# 11_-MAIN_POWER2.net
KiCad netlist of a schematic drawn in Altium Designer
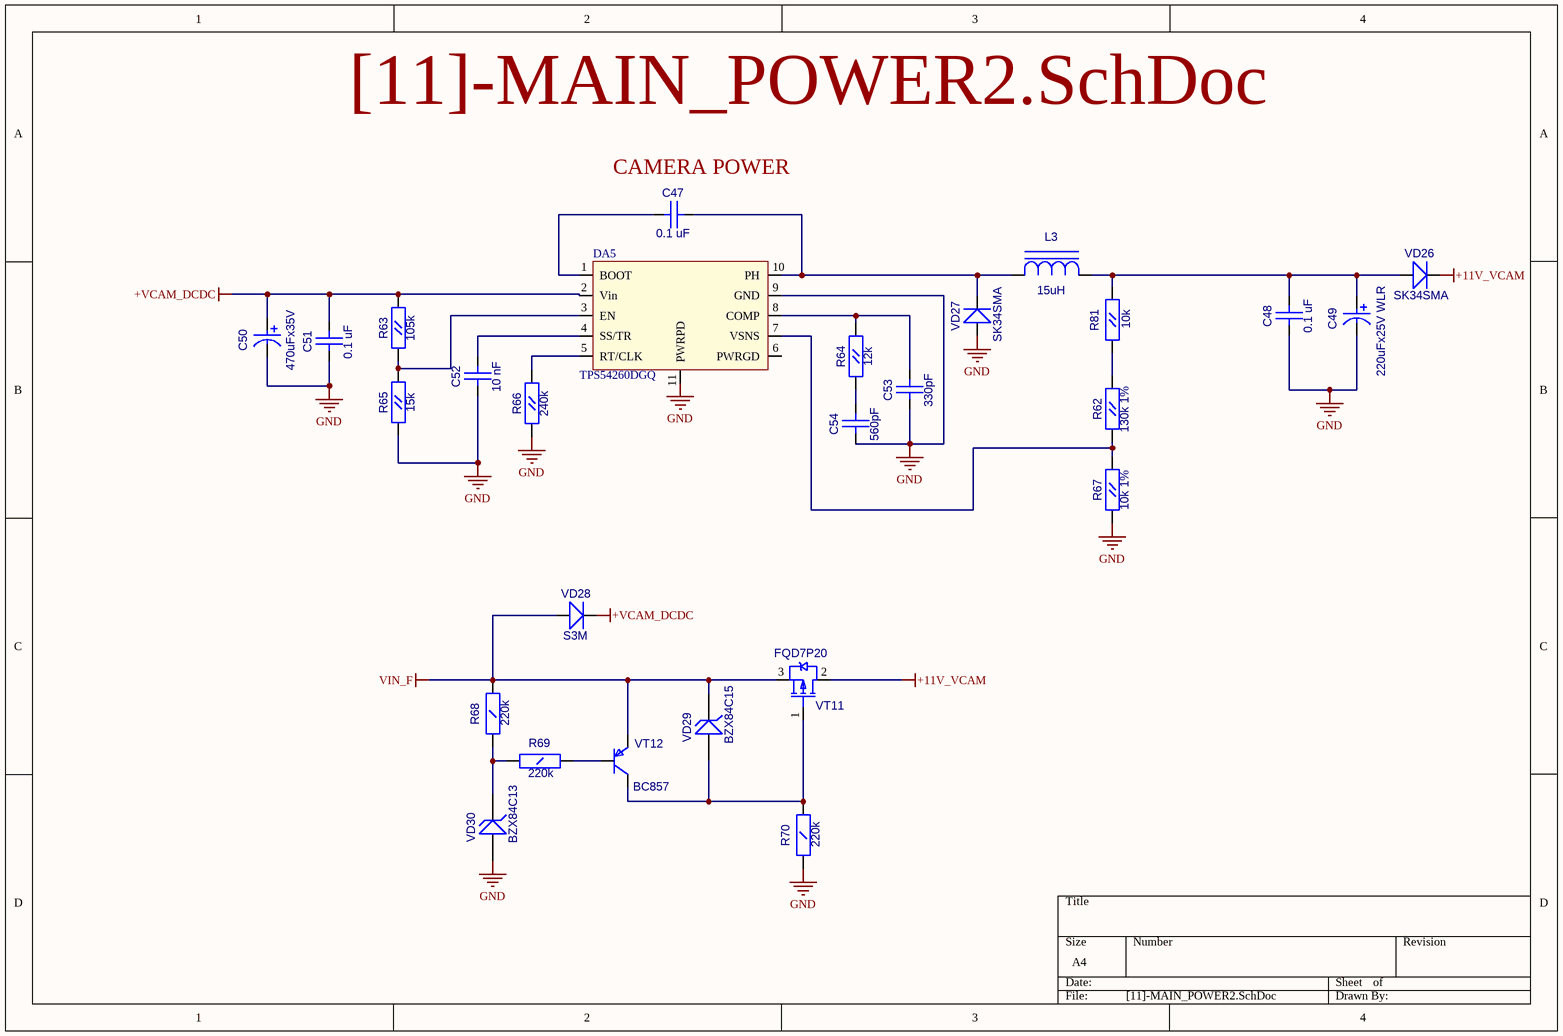
[diagram p0: [11]-MAIN_POWER2.SchDoc]

(export (version "E")
  (design (tool "Eeschema 10.0.6"))
  (components
    (comp (ref "C47")
      (value "0.1 uF")
      (footprint "CC0603")
      (description "CC0603")
      (libsource (lib "gprs_modem_2") (part "CC0603"))
    )
    (comp (ref "C48")
      (value "0.1 uF")
      (footprint "CC0603")
      (description "CC0603")
      (libsource (lib "gprs_modem_2") (part "CC0603"))
    )
    (comp (ref "C49")
      (value "220uFx25V WLR")
      (footprint "CC8X3.5")
      (description "CAP0.35")
      (libsource (lib "gprs_modem_2") (part "CAP0.35"))
    )
    (comp (ref "C50")
      (value "470uFx35V")
      (footprint "CC16X10_CAP0.5(1)(Primary)")
      (description "CAP0.5(1)")
      (libsource (lib "gprs_modem_2") (part "CAP0.5(1)"))
    )
    (comp (ref "C51")
      (value "0.1 uF")
      (footprint "CC0603")
      (description "CC0603")
      (libsource (lib "gprs_modem_2") (part "CC0603"))
    )
    (comp (ref "C52")
      (value "10 nF")
      (footprint "CC0603")
      (description "CC0603")
      (libsource (lib "gprs_modem_2") (part "CC0603"))
    )
    (comp (ref "C53")
      (value "330pF")
      (footprint "CC0603")
      (description "CC0603")
      (libsource (lib "gprs_modem_2") (part "CC0603"))
    )
    (comp (ref "C54")
      (value "560pF")
      (footprint "CC0603")
      (description "CC0603")
      (libsource (lib "gprs_modem_2") (part "CC0603"))
    )
    (comp (ref "DA5")
      (value "TPS54260DGQ")
      (footprint "S-PDSO-G10")
      (libsource (lib "gprs_modem_2") (part "TPS54260DGQ"))
    )
    (comp (ref "L3")
      (value "15uH")
      (footprint "SDR0805")
      (description "SDR0805")
      (libsource (lib "gprs_modem_2") (part "SDR0805"))
    )
    (comp (ref "R62")
      (value "130k 1%")
      (footprint "RC0603")
      (description "RC0603")
      (libsource (lib "gprs_modem_2") (part "RC0603"))
    )
    (comp (ref "R63")
      (value "105k")
      (footprint "RC0603")
      (description "RC0603")
      (libsource (lib "gprs_modem_2") (part "RC0603"))
    )
    (comp (ref "R64")
      (value "12k")
      (footprint "RC0603")
      (description "RC0603")
      (libsource (lib "gprs_modem_2") (part "RC0603"))
    )
    (comp (ref "R65")
      (value "15k")
      (footprint "RC0603")
      (description "RC0603")
      (libsource (lib "gprs_modem_2") (part "RC0603"))
    )
    (comp (ref "R66")
      (value "240k")
      (footprint "RC0603")
      (description "RC0603")
      (libsource (lib "gprs_modem_2") (part "RC0603"))
    )
    (comp (ref "R67")
      (value "10k 1%")
      (footprint "RC0603")
      (description "RC0603")
      (libsource (lib "gprs_modem_2") (part "RC0603"))
    )
    (comp (ref "R68")
      (value "220k")
      (footprint "RC1206")
      (description "RC1206")
      (libsource (lib "fizik_lib") (part "RC1206"))
    )
    (comp (ref "R69")
      (value "220k")
      (footprint "RC1206")
      (description "RC1206")
      (libsource (lib "fizik_lib") (part "RC1206"))
    )
    (comp (ref "R70")
      (value "220k")
      (footprint "RC1206")
      (description "RC1206")
      (libsource (lib "fizik_lib") (part "RC1206"))
    )
    (comp (ref "R81")
      (value "10k")
      (footprint "RC0603")
      (description "RC0603")
      (libsource (lib "fizik_lib") (part "RC0603"))
    )
    (comp (ref "VD26")
      (value "SK34SMA")
      (footprint "SMA")
      (description "Schottky Rectifier")
      (libsource (lib "gprs_modem") (part "SK34SMA"))
    )
    (comp (ref "VD27")
      (value "SK34SMA")
      (footprint "SMA")
      (description "Schottky Rectifier")
      (libsource (lib "gprs_modem") (part "SK34SMA"))
    )
    (comp (ref "VD28")
      (value "S3M")
      (footprint "SMC")
      (description "Schottky Rectifier")
      (libsource (lib "fizik_lib") (part "S3A"))
    )
    (comp (ref "VD29")
      (value "BZX84C15")
      (footprint "SOT-23(123)")
      (description "Zener Voltage Regulator Diode")
      (libsource (lib "fizik_lib") (part "BZX84"))
    )
    (comp (ref "VD30")
      (value "BZX84C13")
      (footprint "SOT-23(123)")
      (description "Zener Voltage Regulator Diode")
      (libsource (lib "fizik_lib") (part "BZX84"))
    )
    (comp (ref "VT11")
      (value "FQD7P20")
      (footprint "D-PAK(TO-252AA)")
      (description "HEXFET Power MOSFET")
      (libsource (lib "gprs_modem_2") (part "IRFR9220"))
    )
    (comp (ref "VT12")
      (value "BC857")
      (footprint "SOT-23(123)")
      (description "PNP 100ma transistor")
      (libsource (lib "gprs_modem_2") (part "BC857B"))
    )
  )
  (nets
    (net (code "1") (name "+11V_VCAM") (class "Default")
      (node (ref "VD26") (pin "2") (pinfunction "K_2") (pintype "passive"))
      (node (ref "VT11") (pin "2") (pinfunction "D_2") (pintype "passive"))
    )
    (net (code "2") (name "+VCAM_DCDC") (class "Default")
      (node (ref "C50") (pin "2") (pintype "passive"))
      (node (ref "C51") (pin "1") (pinfunction "A_1") (pintype "passive"))
      (node (ref "DA5") (pin "2") (pinfunction "Vin_2") (pintype "passive"))
      (node (ref "R63") (pin "2") (pinfunction "B_2") (pintype "passive"))
      (node (ref "VD28") (pin "2") (pinfunction "K_2") (pintype "passive"))
    )
    (net (code "3") (name "GND") (class "Default")
      (node (ref "C48") (pin "2") (pinfunction "B_2") (pintype "passive"))
      (node (ref "C49") (pin "2") (pintype "passive"))
      (node (ref "C50") (pin "1") (pintype "passive"))
      (node (ref "C51") (pin "2") (pinfunction "B_2") (pintype "passive"))
      (node (ref "C52") (pin "2") (pinfunction "B_2") (pintype "passive"))
      (node (ref "C53") (pin "2") (pinfunction "B_2") (pintype "passive"))
      (node (ref "C54") (pin "2") (pinfunction "B_2") (pintype "passive"))
      (node (ref "DA5") (pin "11") (pinfunction "PWRPD_11") (pintype "passive"))
      (node (ref "DA5") (pin "9") (pinfunction "GND_9") (pintype "passive"))
      (node (ref "R65") (pin "1") (pinfunction "A_1") (pintype "passive"))
      (node (ref "R66") (pin "1") (pinfunction "A_1") (pintype "passive"))
      (node (ref "R67") (pin "1") (pinfunction "A_1") (pintype "passive"))
      (node (ref "R70") (pin "1") (pinfunction "A_1") (pintype "passive"))
      (node (ref "VD27") (pin "1") (pinfunction "A_1") (pintype "passive"))
      (node (ref "VD30") (pin "1") (pinfunction "A_1") (pintype "passive"))
    )
    (net (code "4") (name "Net-(C47-A)") (class "Default")
      (node (ref "C47") (pin "1") (pinfunction "A_1") (pintype "passive"))
      (node (ref "DA5") (pin "10") (pinfunction "PH_10") (pintype "passive"))
      (node (ref "L3") (pin "1") (pinfunction "C_1") (pintype "passive"))
      (node (ref "VD27") (pin "2") (pinfunction "K_2") (pintype "passive"))
    )
    (net (code "5") (name "Net-(C47-B)") (class "Default")
      (node (ref "C47") (pin "2") (pinfunction "B_2") (pintype "passive"))
      (node (ref "DA5") (pin "1") (pinfunction "BOOT_1") (pintype "passive"))
    )
    (net (code "6") (name "Net-(C48-A)") (class "Default")
      (node (ref "C48") (pin "1") (pinfunction "A_1") (pintype "passive"))
      (node (ref "C49") (pin "1") (pintype "passive"))
      (node (ref "L3") (pin "2") (pinfunction "A_2") (pintype "passive"))
      (node (ref "R81") (pin "2") (pinfunction "B_2") (pintype "passive"))
      (node (ref "VD26") (pin "1") (pinfunction "A_1") (pintype "passive"))
    )
    (net (code "7") (name "Net-(C52-A)") (class "Default")
      (node (ref "C52") (pin "1") (pinfunction "A_1") (pintype "passive"))
      (node (ref "DA5") (pin "4") (pinfunction "SS/TR_4") (pintype "passive"))
    )
    (net (code "8") (name "Net-(C53-A)") (class "Default")
      (node (ref "C53") (pin "1") (pinfunction "A_1") (pintype "passive"))
      (node (ref "DA5") (pin "8") (pinfunction "COMP_8") (pintype "passive"))
      (node (ref "R64") (pin "2") (pinfunction "B_2") (pintype "passive"))
    )
    (net (code "9") (name "Net-(C54-A)") (class "Default")
      (node (ref "C54") (pin "1") (pinfunction "A_1") (pintype "passive"))
      (node (ref "R64") (pin "1") (pinfunction "A_1") (pintype "passive"))
    )
    (net (code "10") (name "Net-(DA5-EN)") (class "Default")
      (node (ref "DA5") (pin "3") (pinfunction "EN_3") (pintype "passive"))
      (node (ref "R63") (pin "1") (pinfunction "A_1") (pintype "passive"))
      (node (ref "R65") (pin "2") (pinfunction "B_2") (pintype "passive"))
    )
    (net (code "11") (name "Net-(DA5-RT{slash}CLK)") (class "Default")
      (node (ref "DA5") (pin "5") (pinfunction "RT/CLK_5") (pintype "passive"))
      (node (ref "R66") (pin "2") (pinfunction "B_2") (pintype "passive"))
    )
    (net (code "12") (name "Net-(DA5-VSNS)") (class "Default")
      (node (ref "DA5") (pin "7") (pinfunction "VSNS_7") (pintype "passive"))
      (node (ref "R62") (pin "1") (pinfunction "A_1") (pintype "passive"))
      (node (ref "R67") (pin "2") (pinfunction "B_2") (pintype "passive"))
    )
    (net (code "13") (name "Net-(R62-B)") (class "Default")
      (node (ref "R62") (pin "2") (pinfunction "B_2") (pintype "passive"))
      (node (ref "R81") (pin "1") (pinfunction "A_1") (pintype "passive"))
    )
    (net (code "14") (name "Net-(R68-A)") (class "Default")
      (node (ref "R68") (pin "1") (pinfunction "A_1") (pintype "passive"))
      (node (ref "R69") (pin "1") (pinfunction "A_1") (pintype "passive"))
      (node (ref "VD30") (pin "3") (pinfunction "K_3") (pintype "passive"))
    )
    (net (code "15") (name "Net-(R69-B)") (class "Default")
      (node (ref "R69") (pin "2") (pinfunction "B_2") (pintype "passive"))
      (node (ref "VT12") (pin "1") (pinfunction "B_1") (pintype "passive"))
    )
    (net (code "16") (name "Net-(R70-B)") (class "Default")
      (node (ref "R70") (pin "2") (pinfunction "B_2") (pintype "passive"))
      (node (ref "VD29") (pin "1") (pinfunction "A_1") (pintype "passive"))
      (node (ref "VT11") (pin "1") (pinfunction "G_1") (pintype "passive"))
      (node (ref "VT12") (pin "3") (pinfunction "C_3") (pintype "passive"))
    )
    (net (code "17") (name "VIN_F") (class "Default")
      (node (ref "R68") (pin "2") (pinfunction "B_2") (pintype "passive"))
      (node (ref "VD28") (pin "1") (pinfunction "A_1") (pintype "passive"))
      (node (ref "VD29") (pin "3") (pinfunction "K_3") (pintype "passive"))
      (node (ref "VT11") (pin "3") (pinfunction "S_3") (pintype "passive"))
      (node (ref "VT12") (pin "2") (pinfunction "E_2") (pintype "passive"))
    )
    (net (code "18") (name "unconnected-(DA5-PWRGD-Pad6)") (class "Default")
      (node (ref "DA5") (pin "6") (pinfunction "PWRGD_6") (pintype "passive"))
    )
  )
)
